# Driver6.net
KiCad netlist of a schematic drawn in Altium Designer
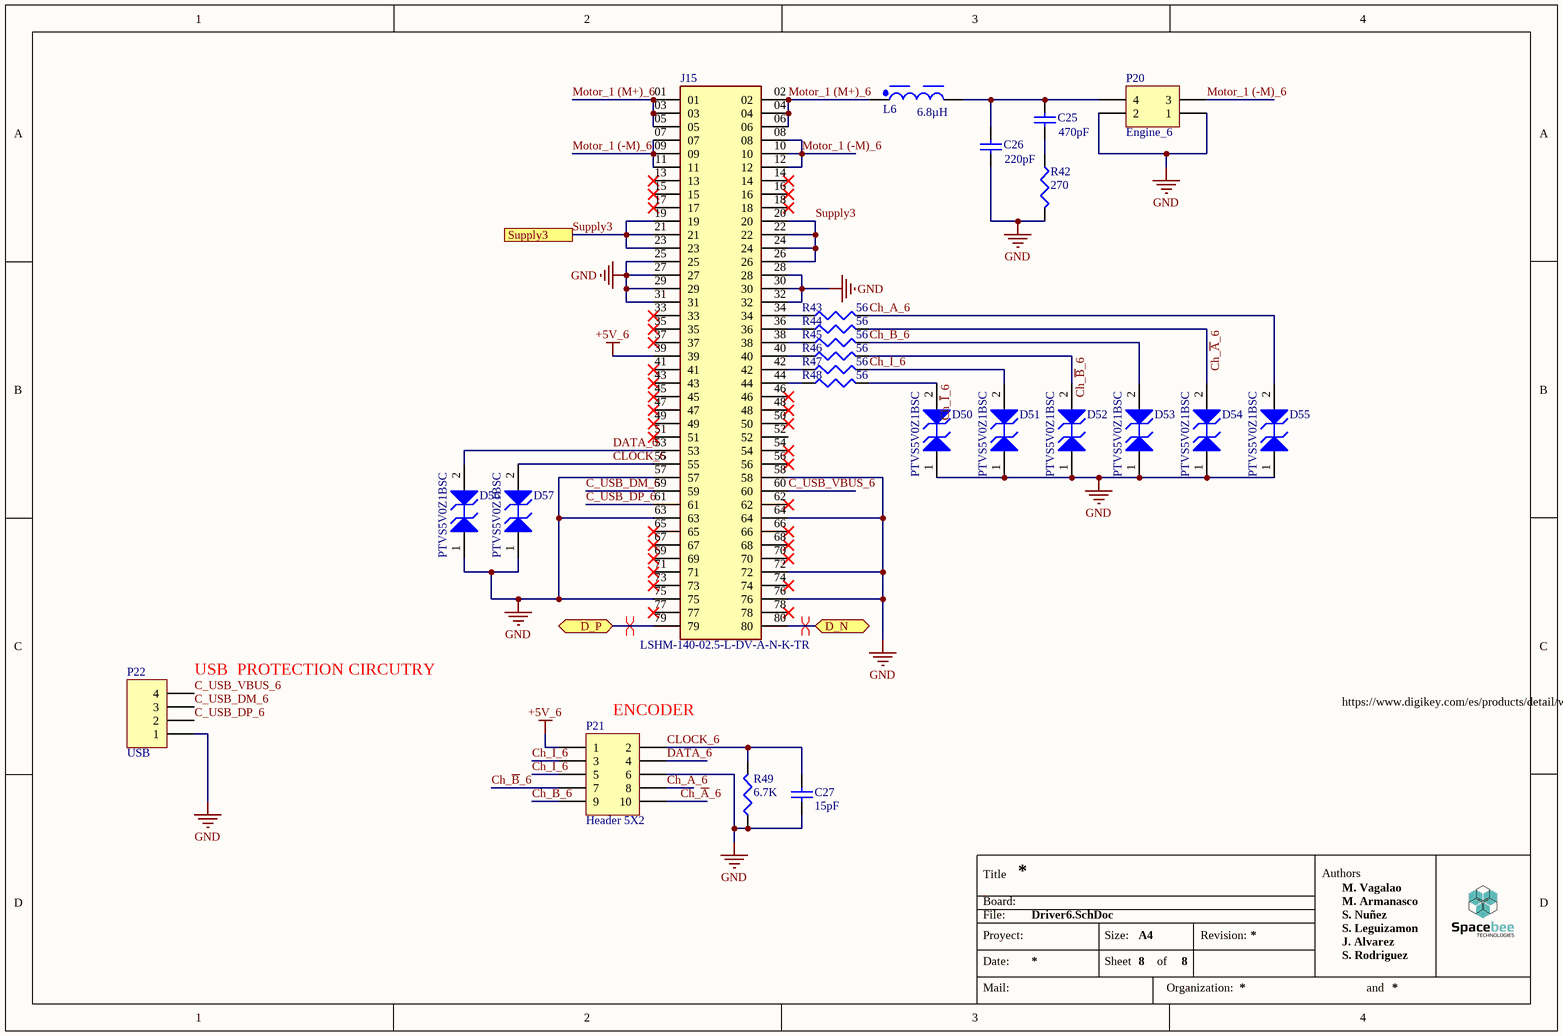
[diagram p0: Driver6.SchDoc]

(export (version "E")
  (design (tool "Eeschema 10.0.6"))
  (components
    (comp (ref "C25")
      (value "470pF")
      (footprint "1608[0603]")
      (description "Capacitor (Semiconductor SIM Model)")
      (fields (field (name "Comment") "Cap Semi") (field (name "PUBLISHER") "Altium Limited"))
      (libsource (lib "Miscellaneous Devices") (part "Cap Semi"))
    )
    (comp (ref "C26")
      (value "220pF")
      (footprint "1608[0603]")
      (description "Capacitor (Semiconductor SIM Model)")
      (fields (field (name "Comment") "Cap Semi") (field (name "PUBLISHER") "Altium Limited"))
      (libsource (lib "Miscellaneous Devices") (part "Cap Semi"))
    )
    (comp (ref "C27")
      (value "15pF")
      (footprint "6-0805_L")
      (description "Capacitor (Semiconductor SIM Model)")
      (fields (field (name "Comment") "Cap Semi") (field (name "PUBLISHER") "Altium Limited"))
      (libsource (lib "SpaceBee") (part "Cap 0805"))
    )
    (comp (ref "D50")
      (value "PTVS5V0Z1BSC")
      (footprint "SOD993B")
      (fields (field (name "MANUFACTURER") "On Semiconductor") (field (name "PARTNUMBER") "1SMB16CAT3"))
      (libsource (lib "DriverLib") (part "PTVS5V0Z1BSC"))
    )
    (comp (ref "D51")
      (value "PTVS5V0Z1BSC")
      (footprint "SOD993B")
      (fields (field (name "MANUFACTURER") "On Semiconductor") (field (name "PARTNUMBER") "1SMB16CAT3"))
      (libsource (lib "DriverLib") (part "PTVS5V0Z1BSC"))
    )
    (comp (ref "D52")
      (value "PTVS5V0Z1BSC")
      (footprint "SOD993B")
      (fields (field (name "MANUFACTURER") "On Semiconductor") (field (name "PARTNUMBER") "1SMB16CAT3"))
      (libsource (lib "DriverLib") (part "PTVS5V0Z1BSC"))
    )
    (comp (ref "D53")
      (value "PTVS5V0Z1BSC")
      (footprint "SOD993B")
      (fields (field (name "MANUFACTURER") "On Semiconductor") (field (name "PARTNUMBER") "1SMB16CAT3"))
      (libsource (lib "DriverLib") (part "PTVS5V0Z1BSC"))
    )
    (comp (ref "D54")
      (value "PTVS5V0Z1BSC")
      (footprint "SOD993B")
      (fields (field (name "MANUFACTURER") "On Semiconductor") (field (name "PARTNUMBER") "1SMB16CAT3"))
      (libsource (lib "DriverLib") (part "PTVS5V0Z1BSC"))
    )
    (comp (ref "D55")
      (value "PTVS5V0Z1BSC")
      (footprint "SOD993B")
      (fields (field (name "MANUFACTURER") "On Semiconductor") (field (name "PARTNUMBER") "1SMB16CAT3"))
      (libsource (lib "DriverLib") (part "PTVS5V0Z1BSC"))
    )
    (comp (ref "D56")
      (value "PTVS5V0Z1BSC")
      (footprint "SOD993B")
      (fields (field (name "MANUFACTURER") "On Semiconductor") (field (name "PARTNUMBER") "1SMB16CAT3"))
      (libsource (lib "DriverLib") (part "PTVS5V0Z1BSC"))
    )
    (comp (ref "D57")
      (value "PTVS5V0Z1BSC")
      (footprint "SOD993B")
      (fields (field (name "MANUFACTURER") "On Semiconductor") (field (name "PARTNUMBER") "1SMB16CAT3"))
      (libsource (lib "DriverLib") (part "PTVS5V0Z1BSC"))
    )
    (comp (ref "J15")
      (value "LSHM-140-02.5-L-DV-A-N-K-TR")
      (footprint "SAMTEC_LSHM-140-02.5-L-DV-A-N-K-TR")
      (description "LSHM - Samtec 0.50mm Razor Beam High-Speed Hermaphroditic Terminal / Socket Strip.")
      (libsource (lib "DriverLib") (part "LSHM-140-02.5-L-DV-A-N-K-TR"))
    )
    (comp (ref "L6")
      (value "6.8µH")
      (footprint "WE-XHMA_6060")
      (description "WE-XHMA SMD Power Inductor, size 1090, 6.8µH, 10.5A, 7.16mΩ")
      (fields
        (field (name "MANUFACTURER PART NUMBER") "78439369068")
        (field (name "MANUFACTURER") "Wurth Elektronik")
      )
      (libsource (lib "DriverLib") (part "78439369068"))
    )
    (comp (ref "P20")
      (value "Engine_6")
      (footprint "MOLEX_1724480004")
      (description "Header, 2-Pin, Dual row")
      (fields (field (name "PUBLISHER") "Altium Limited"))
      (libsource (lib "SpaceBee") (part "Header 2X2"))
    )
    (comp (ref "P21")
      (value "Header 5X2")
      (footprint "CONN_HIF3FC-14PA-2.54DS(71)_HIR")
      (description "Header, 5-Pin, Dual row")
      (fields (field (name "PUBLISHER") "Altium Limited"))
      (libsource (lib "DriverLib") (part "Header 5X2"))
    )
    (comp (ref "P22")
      (value "USB")
      (footprint "Header 4 SMD")
      (description "Header, 4-Pin")
      (fields (field (name "PUBLISHER") "Altium Limited"))
      (libsource (lib "SpaceBee") (part "Header 4 SMD"))
    )
    (comp (ref "R42")
      (value "270")
      (footprint "J1-0603")
      (description "Resistor")
      (fields (field (name "Comment") "Res3") (field (name "PUBLISHER") "Altium Limited"))
      (libsource (lib "Miscellaneous Devices") (part "Res3"))
    )
    (comp (ref "R43")
      (value "56")
      (footprint "J1-0603")
      (description "Resistor")
      (fields (field (name "Comment") "Res3") (field (name "PUBLISHER") "Altium Limited"))
      (libsource (lib "Miscellaneous Devices") (part "Res3"))
    )
    (comp (ref "R44")
      (value "56")
      (footprint "J1-0603")
      (description "Resistor")
      (fields (field (name "Comment") "Res3") (field (name "PUBLISHER") "Altium Limited"))
      (libsource (lib "Miscellaneous Devices") (part "Res3"))
    )
    (comp (ref "R45")
      (value "56")
      (footprint "J1-0603")
      (description "Resistor")
      (fields (field (name "Comment") "Res3") (field (name "PUBLISHER") "Altium Limited"))
      (libsource (lib "Miscellaneous Devices") (part "Res3"))
    )
    (comp (ref "R46")
      (value "56")
      (footprint "J1-0603")
      (description "Resistor")
      (fields (field (name "Comment") "Res3") (field (name "PUBLISHER") "Altium Limited"))
      (libsource (lib "Miscellaneous Devices") (part "Res3"))
    )
    (comp (ref "R47")
      (value "56")
      (footprint "J1-0603")
      (description "Resistor")
      (fields (field (name "Comment") "Res3") (field (name "PUBLISHER") "Altium Limited"))
      (libsource (lib "Miscellaneous Devices") (part "Res3"))
    )
    (comp (ref "R48")
      (value "56")
      (footprint "J1-0603")
      (description "Resistor")
      (fields (field (name "Comment") "Res3") (field (name "PUBLISHER") "Altium Limited"))
      (libsource (lib "Miscellaneous Devices") (part "Res3"))
    )
    (comp (ref "R49")
      (value "6.7K")
      (footprint "J1-0603")
      (description "Resistor")
      (fields (field (name "Comment") "Res3") (field (name "PUBLISHER") "Altium Limited"))
      (libsource (lib "Miscellaneous Devices") (part "Res3"))
    )
  )
  (nets
    (net (code "1") (name "+5V_6") (class "Default")
      (node (ref "J15") (pin "39") (pinfunction "39_39") (pintype "passive"))
      (node (ref "P21") (pin "1") (pinfunction "1_1") (pintype "passive"))
    )
    (net (code "2") (name "/CLOCK_6") (class "Default")
      (node (ref "C27") (pin "2") (pinfunction "2_2") (pintype "passive"))
      (node (ref "D57") (pin "2") (pinfunction "A2_2") (pintype "passive"))
      (node (ref "J15") (pin "55") (pinfunction "55_55") (pintype "passive"))
      (node (ref "P21") (pin "2") (pinfunction "2_2") (pintype "passive"))
      (node (ref "R49") (pin "2") (pinfunction "2_2") (pintype "passive"))
    )
    (net (code "3") (name "/C_USB_DM_6") (class "Default")
      (node (ref "J15") (pin "59") (pinfunction "59_59") (pintype "passive"))
      (node (ref "P22") (pin "3") (pinfunction "3_3") (pintype "passive"))
    )
    (net (code "4") (name "/C_USB_DP_6") (class "Default")
      (node (ref "J15") (pin "61") (pinfunction "61_61") (pintype "passive"))
      (node (ref "P22") (pin "2") (pinfunction "2_2") (pintype "passive"))
    )
    (net (code "5") (name "/C_USB_VBUS_6") (class "Default")
      (node (ref "J15") (pin "60") (pinfunction "60_60") (pintype "passive"))
      (node (ref "P22") (pin "4") (pinfunction "4_4") (pintype "passive"))
    )
    (net (code "6") (name "/Ch_A_6") (class "Default")
      (node (ref "D55") (pin "2") (pinfunction "A2_2") (pintype "passive"))
      (node (ref "P21") (pin "8") (pinfunction "8_8") (pintype "passive"))
      (node (ref "R43") (pin "2") (pinfunction "2_2") (pintype "passive"))
    )
    (net (code "7") (name "/Ch_B_6") (class "Default")
      (node (ref "D53") (pin "2") (pinfunction "A2_2") (pintype "passive"))
      (node (ref "P21") (pin "9") (pinfunction "9_9") (pintype "passive"))
      (node (ref "R45") (pin "2") (pinfunction "2_2") (pintype "passive"))
    )
    (net (code "8") (name "/Ch_I_6") (class "Default")
      (node (ref "D51") (pin "2") (pinfunction "A2_2") (pintype "passive"))
      (node (ref "P21") (pin "5") (pinfunction "5_5") (pintype "passive"))
      (node (ref "R47") (pin "2") (pinfunction "2_2") (pintype "passive"))
    )
    (net (code "9") (name "/Ch_~{A}_6") (class "Default")
      (node (ref "D54") (pin "2") (pinfunction "A2_2") (pintype "passive"))
      (node (ref "P21") (pin "10") (pinfunction "10_10") (pintype "passive"))
      (node (ref "R44") (pin "2") (pinfunction "2_2") (pintype "passive"))
    )
    (net (code "10") (name "/Ch_~{B}_6") (class "Default")
      (node (ref "D52") (pin "2") (pinfunction "A2_2") (pintype "passive"))
      (node (ref "P21") (pin "7") (pinfunction "7_7") (pintype "passive"))
      (node (ref "R46") (pin "2") (pinfunction "2_2") (pintype "passive"))
    )
    (net (code "11") (name "/Ch_~{I}_6") (class "Default")
      (node (ref "D50") (pin "2") (pinfunction "A2_2") (pintype "passive"))
      (node (ref "P21") (pin "3") (pinfunction "3_3") (pintype "passive"))
      (node (ref "R48") (pin "2") (pinfunction "2_2") (pintype "passive"))
    )
    (net (code "12") (name "/DATA_6") (class "Default")
      (node (ref "D56") (pin "2") (pinfunction "A2_2") (pintype "passive"))
      (node (ref "J15") (pin "53") (pinfunction "53_53") (pintype "passive"))
      (node (ref "P21") (pin "4") (pinfunction "4_4") (pintype "passive"))
    )
    (net (code "13") (name "/D_N") (class "Default")
      (node (ref "J15") (pin "80") (pinfunction "80_80") (pintype "passive"))
    )
    (net (code "14") (name "/D_P") (class "Default")
      (node (ref "J15") (pin "79") (pinfunction "79_79") (pintype "passive"))
    )
    (net (code "15") (name "/Motor_1 (-M)_6") (class "Default")
      (node (ref "J15") (pin "07") (pinfunction "07_07") (pintype "passive"))
      (node (ref "J15") (pin "08") (pinfunction "08_08") (pintype "passive"))
      (node (ref "J15") (pin "09") (pinfunction "09_09") (pintype "passive"))
      (node (ref "J15") (pin "10") (pinfunction "10_10") (pintype "passive"))
      (node (ref "J15") (pin "11") (pinfunction "11_11") (pintype "passive"))
      (node (ref "J15") (pin "12") (pinfunction "12_12") (pintype "passive"))
      (node (ref "P20") (pin "3") (pinfunction "3_3") (pintype "passive"))
    )
    (net (code "16") (name "/Motor_1 (M+)_6") (class "Default")
      (node (ref "J15") (pin "01") (pinfunction "01_01") (pintype "passive"))
      (node (ref "J15") (pin "02") (pinfunction "02_02") (pintype "passive"))
      (node (ref "J15") (pin "03") (pinfunction "03_03") (pintype "passive"))
      (node (ref "J15") (pin "04") (pinfunction "04_04") (pintype "passive"))
      (node (ref "J15") (pin "05") (pinfunction "05_05") (pintype "passive"))
      (node (ref "J15") (pin "06") (pinfunction "06_06") (pintype "passive"))
      (node (ref "L6") (pin "1") (pinfunction "1_1") (pintype "passive"))
    )
    (net (code "17") (name "/Supply3") (class "Default")
      (node (ref "J15") (pin "19") (pinfunction "19_19") (pintype "passive"))
      (node (ref "J15") (pin "20") (pinfunction "20_20") (pintype "passive"))
      (node (ref "J15") (pin "21") (pinfunction "21_21") (pintype "passive"))
      (node (ref "J15") (pin "22") (pinfunction "22_22") (pintype "passive"))
      (node (ref "J15") (pin "23") (pinfunction "23_23") (pintype "passive"))
      (node (ref "J15") (pin "24") (pinfunction "24_24") (pintype "passive"))
      (node (ref "J15") (pin "26") (pinfunction "26_26") (pintype "passive"))
    )
    (net (code "18") (name "GND") (class "Default")
      (node (ref "C26") (pin "2") (pinfunction "2_2") (pintype "passive"))
      (node (ref "C27") (pin "1") (pinfunction "1_1") (pintype "passive"))
      (node (ref "D50") (pin "1") (pinfunction "A1_1") (pintype "passive"))
      (node (ref "D51") (pin "1") (pinfunction "A1_1") (pintype "passive"))
      (node (ref "D52") (pin "1") (pinfunction "A1_1") (pintype "passive"))
      (node (ref "D53") (pin "1") (pinfunction "A1_1") (pintype "passive"))
      (node (ref "D54") (pin "1") (pinfunction "A1_1") (pintype "passive"))
      (node (ref "D55") (pin "1") (pinfunction "A1_1") (pintype "passive"))
      (node (ref "D56") (pin "1") (pinfunction "A1_1") (pintype "passive"))
      (node (ref "D57") (pin "1") (pinfunction "A1_1") (pintype "passive"))
      (node (ref "J15") (pin "25") (pinfunction "25_25") (pintype "passive"))
      (node (ref "J15") (pin "27") (pinfunction "27_27") (pintype "passive"))
      (node (ref "J15") (pin "28") (pinfunction "28_28") (pintype "passive"))
      (node (ref "J15") (pin "29") (pinfunction "29_29") (pintype "passive"))
      (node (ref "J15") (pin "30") (pinfunction "30_30") (pintype "passive"))
      (node (ref "J15") (pin "31") (pinfunction "31_31") (pintype "passive"))
      (node (ref "J15") (pin "32") (pinfunction "32_32") (pintype "passive"))
      (node (ref "J15") (pin "57") (pinfunction "57_57") (pintype "passive"))
      (node (ref "J15") (pin "58") (pinfunction "58_58") (pintype "passive"))
      (node (ref "J15") (pin "63") (pinfunction "63_63") (pintype "passive"))
      (node (ref "J15") (pin "64") (pinfunction "64_64") (pintype "passive"))
      (node (ref "J15") (pin "72") (pinfunction "72_72") (pintype "passive"))
      (node (ref "J15") (pin "75") (pinfunction "75_75") (pintype "passive"))
      (node (ref "J15") (pin "76") (pinfunction "76_76") (pintype "passive"))
      (node (ref "P20") (pin "1") (pinfunction "1_1") (pintype "passive"))
      (node (ref "P20") (pin "2") (pinfunction "2_2") (pintype "passive"))
      (node (ref "P21") (pin "6") (pinfunction "6_6") (pintype "passive"))
      (node (ref "P22") (pin "1") (pinfunction "1_1") (pintype "passive"))
      (node (ref "R42") (pin "2") (pinfunction "2_2") (pintype "passive"))
      (node (ref "R49") (pin "1") (pinfunction "1_1") (pintype "passive"))
    )
    (net (code "19") (name "Net-(C25-Pad1)") (class "Default")
      (node (ref "C25") (pin "1") (pinfunction "1_1") (pintype "passive"))
      (node (ref "C26") (pin "1") (pinfunction "1_1") (pintype "passive"))
      (node (ref "L6") (pin "2") (pinfunction "2_2") (pintype "passive"))
      (node (ref "P20") (pin "4") (pinfunction "4_4") (pintype "passive"))
    )
    (net (code "20") (name "Net-(C25-Pad2)") (class "Default")
      (node (ref "C25") (pin "2") (pinfunction "2_2") (pintype "passive"))
      (node (ref "R42") (pin "1") (pinfunction "1_1") (pintype "passive"))
    )
    (net (code "21") (name "Net-(J15-Pad34)") (class "Default")
      (node (ref "J15") (pin "34") (pinfunction "34_34") (pintype "passive"))
      (node (ref "R43") (pin "1") (pinfunction "1_1") (pintype "passive"))
    )
    (net (code "22") (name "Net-(J15-Pad36)") (class "Default")
      (node (ref "J15") (pin "36") (pinfunction "36_36") (pintype "passive"))
      (node (ref "R44") (pin "1") (pinfunction "1_1") (pintype "passive"))
    )
    (net (code "23") (name "Net-(J15-Pad38)") (class "Default")
      (node (ref "J15") (pin "38") (pinfunction "38_38") (pintype "passive"))
      (node (ref "R45") (pin "1") (pinfunction "1_1") (pintype "passive"))
    )
    (net (code "24") (name "Net-(J15-Pad40)") (class "Default")
      (node (ref "J15") (pin "40") (pinfunction "40_40") (pintype "passive"))
      (node (ref "R46") (pin "1") (pinfunction "1_1") (pintype "passive"))
    )
    (net (code "25") (name "Net-(J15-Pad42)") (class "Default")
      (node (ref "J15") (pin "42") (pinfunction "42_42") (pintype "passive"))
      (node (ref "R47") (pin "1") (pinfunction "1_1") (pintype "passive"))
    )
    (net (code "26") (name "Net-(J15-Pad44)") (class "Default")
      (node (ref "J15") (pin "44") (pinfunction "44_44") (pintype "passive"))
      (node (ref "R48") (pin "1") (pinfunction "1_1") (pintype "passive"))
    )
    (net (code "27") (name "unconnected-(J15-Pad13)") (class "Default")
      (node (ref "J15") (pin "13") (pinfunction "13_13") (pintype "passive+no_connect"))
    )
    (net (code "28") (name "unconnected-(J15-Pad14)") (class "Default")
      (node (ref "J15") (pin "14") (pinfunction "14_14") (pintype "passive+no_connect"))
    )
    (net (code "29") (name "unconnected-(J15-Pad15)") (class "Default")
      (node (ref "J15") (pin "15") (pinfunction "15_15") (pintype "passive+no_connect"))
    )
    (net (code "30") (name "unconnected-(J15-Pad16)") (class "Default")
      (node (ref "J15") (pin "16") (pinfunction "16_16") (pintype "passive+no_connect"))
    )
    (net (code "31") (name "unconnected-(J15-Pad17)") (class "Default")
      (node (ref "J15") (pin "17") (pinfunction "17_17") (pintype "passive+no_connect"))
    )
    (net (code "32") (name "unconnected-(J15-Pad18)") (class "Default")
      (node (ref "J15") (pin "18") (pinfunction "18_18") (pintype "passive+no_connect"))
    )
    (net (code "33") (name "unconnected-(J15-Pad33)") (class "Default")
      (node (ref "J15") (pin "33") (pinfunction "33_33") (pintype "passive+no_connect"))
    )
    (net (code "34") (name "unconnected-(J15-Pad35)") (class "Default")
      (node (ref "J15") (pin "35") (pinfunction "35_35") (pintype "passive+no_connect"))
    )
    (net (code "35") (name "unconnected-(J15-Pad37)") (class "Default")
      (node (ref "J15") (pin "37") (pinfunction "37_37") (pintype "passive+no_connect"))
    )
    (net (code "36") (name "unconnected-(J15-Pad41)") (class "Default")
      (node (ref "J15") (pin "41") (pinfunction "41_41") (pintype "passive+no_connect"))
    )
    (net (code "37") (name "unconnected-(J15-Pad43)") (class "Default")
      (node (ref "J15") (pin "43") (pinfunction "43_43") (pintype "passive+no_connect"))
    )
    (net (code "38") (name "unconnected-(J15-Pad45)") (class "Default")
      (node (ref "J15") (pin "45") (pinfunction "45_45") (pintype "passive+no_connect"))
    )
    (net (code "39") (name "unconnected-(J15-Pad46)") (class "Default")
      (node (ref "J15") (pin "46") (pinfunction "46_46") (pintype "passive+no_connect"))
    )
    (net (code "40") (name "unconnected-(J15-Pad47)") (class "Default")
      (node (ref "J15") (pin "47") (pinfunction "47_47") (pintype "passive+no_connect"))
    )
    (net (code "41") (name "unconnected-(J15-Pad48)") (class "Default")
      (node (ref "J15") (pin "48") (pinfunction "48_48") (pintype "passive+no_connect"))
    )
    (net (code "42") (name "unconnected-(J15-Pad49)") (class "Default")
      (node (ref "J15") (pin "49") (pinfunction "49_49") (pintype "passive+no_connect"))
    )
    (net (code "43") (name "unconnected-(J15-Pad50)") (class "Default")
      (node (ref "J15") (pin "50") (pinfunction "50_50") (pintype "passive+no_connect"))
    )
    (net (code "44") (name "unconnected-(J15-Pad51)") (class "Default")
      (node (ref "J15") (pin "51") (pinfunction "51_51") (pintype "passive+no_connect"))
    )
    (net (code "45") (name "unconnected-(J15-Pad52)") (class "Default")
      (node (ref "J15") (pin "52") (pinfunction "52_52") (pintype "passive"))
    )
    (net (code "46") (name "unconnected-(J15-Pad54)") (class "Default")
      (node (ref "J15") (pin "54") (pinfunction "54_54") (pintype "passive+no_connect"))
    )
    (net (code "47") (name "unconnected-(J15-Pad56)") (class "Default")
      (node (ref "J15") (pin "56") (pinfunction "56_56") (pintype "passive+no_connect"))
    )
    (net (code "48") (name "unconnected-(J15-Pad62)") (class "Default")
      (node (ref "J15") (pin "62") (pinfunction "62_62") (pintype "passive+no_connect"))
    )
    (net (code "49") (name "unconnected-(J15-Pad65)") (class "Default")
      (node (ref "J15") (pin "65") (pinfunction "65_65") (pintype "passive+no_connect"))
    )
    (net (code "50") (name "unconnected-(J15-Pad66)") (class "Default")
      (node (ref "J15") (pin "66") (pinfunction "66_66") (pintype "passive+no_connect"))
    )
    (net (code "51") (name "unconnected-(J15-Pad67)") (class "Default")
      (node (ref "J15") (pin "67") (pinfunction "67_67") (pintype "passive+no_connect"))
    )
    (net (code "52") (name "unconnected-(J15-Pad68)") (class "Default")
      (node (ref "J15") (pin "68") (pinfunction "68_68") (pintype "passive+no_connect"))
    )
    (net (code "53") (name "unconnected-(J15-Pad69)") (class "Default")
      (node (ref "J15") (pin "69") (pinfunction "69_69") (pintype "passive+no_connect"))
    )
    (net (code "54") (name "unconnected-(J15-Pad70)") (class "Default")
      (node (ref "J15") (pin "70") (pinfunction "70_70") (pintype "passive+no_connect"))
    )
    (net (code "55") (name "unconnected-(J15-Pad71)") (class "Default")
      (node (ref "J15") (pin "71") (pinfunction "71_71") (pintype "passive+no_connect"))
    )
    (net (code "56") (name "unconnected-(J15-Pad73)") (class "Default")
      (node (ref "J15") (pin "73") (pinfunction "73_73") (pintype "passive+no_connect"))
    )
    (net (code "57") (name "unconnected-(J15-Pad74)") (class "Default")
      (node (ref "J15") (pin "74") (pinfunction "74_74") (pintype "passive+no_connect"))
    )
    (net (code "58") (name "unconnected-(J15-Pad77)") (class "Default")
      (node (ref "J15") (pin "77") (pinfunction "77_77") (pintype "passive+no_connect"))
    )
    (net (code "59") (name "unconnected-(J15-Pad78)") (class "Default")
      (node (ref "J15") (pin "78") (pinfunction "78_78") (pintype "passive+no_connect"))
    )
  )
)
